# circuit_BLDCControl.net
KiCad netlist of a schematic drawn in Altium Designer
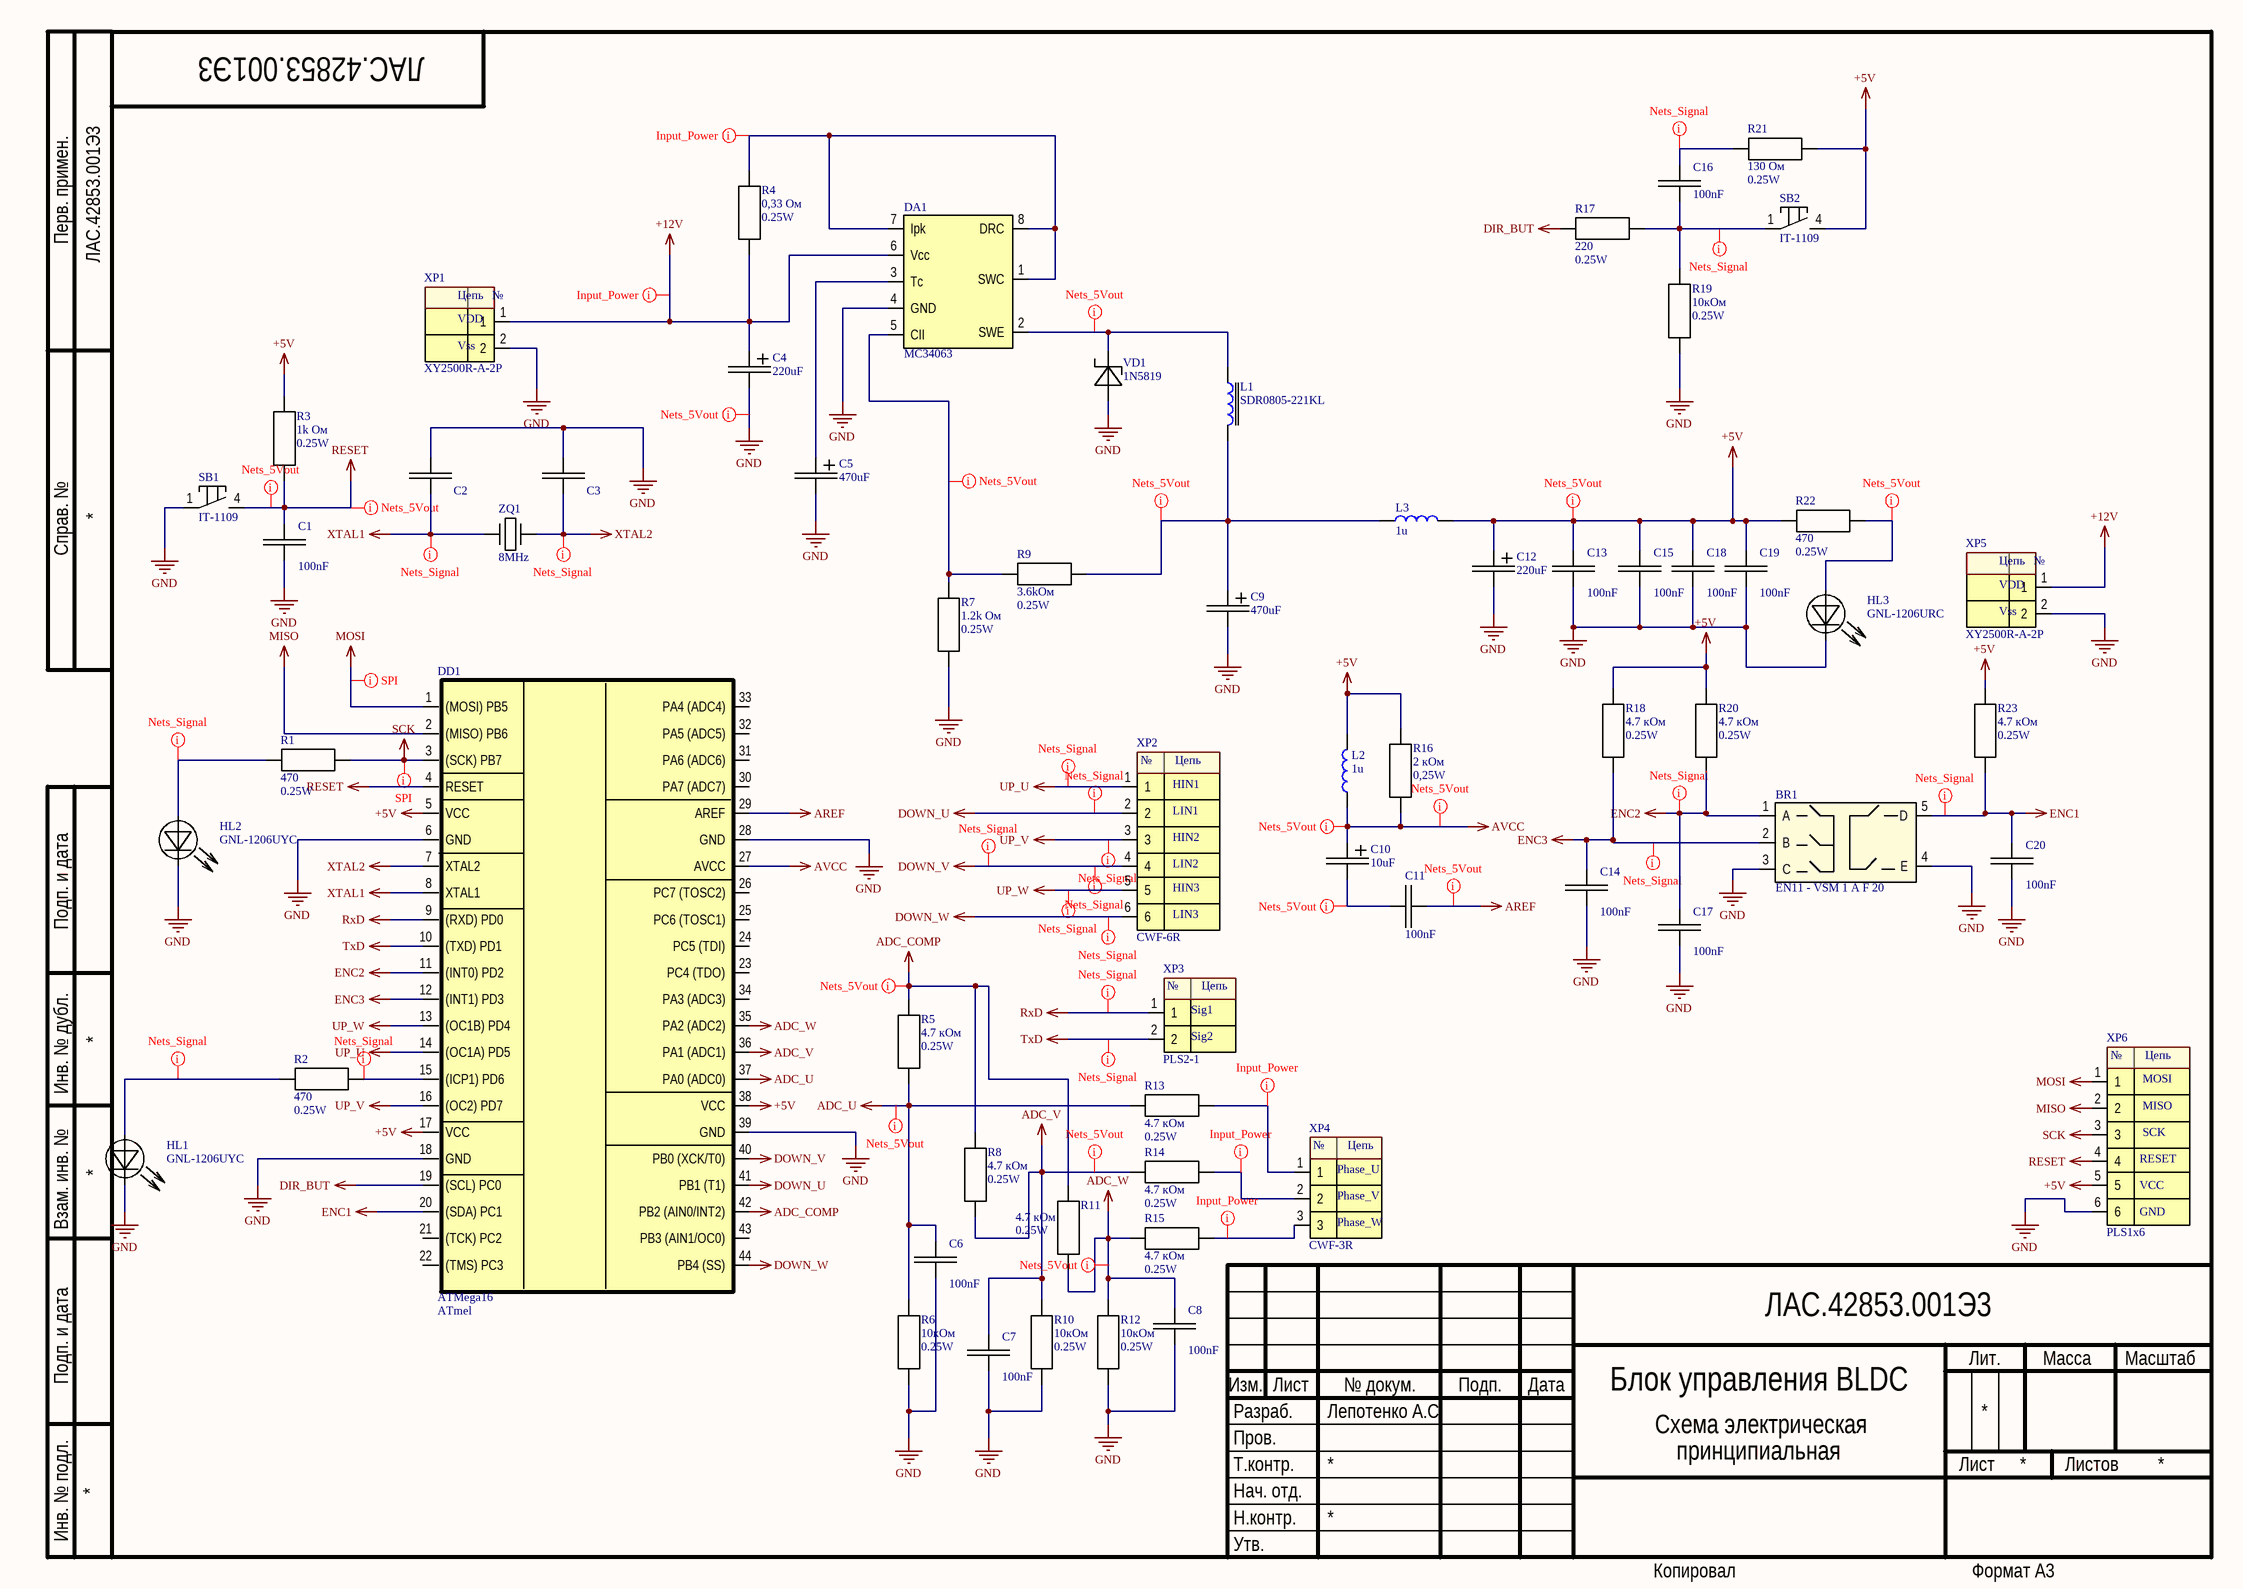
[diagram p0: circuit_BLDCControl.SchDoc]

(export (version "E")
  (design (tool "Eeschema 10.0.6"))
  (components
    (comp (ref "BR1")
      (value "EN11 - VSM 1 A F 20")
      (footprint "EN11-HSM")
      (fields (field (name "MANUFACTURER") "TTelectronics"))
      (libsource (lib "SchlibUGO") (part "Encoder"))
    )
    (comp (ref "C1")
      (value "100nF")
      (footprint "CAP1206")
      (fields
        (field (name "VOLTAGE") "50V")
        (field (name "PART NUMBER") "CL31B104KBCNNNC")
        (field (name "MANUFACTURER") "Samsung")
      )
      (libsource (lib "SchlibUGO") (part "Capasitor"))
    )
    (comp (ref "C2")
      (value "22pF")
      (footprint "CAP1206")
      (fields
        (field (name "VOLTAGE") "50V")
        (field (name "PART NUMBER") "NPO-50V")
        (field (name "MANUFACTURER") "Samsung")
      )
      (libsource (lib "SchlibUGO") (part "Capasitor"))
    )
    (comp (ref "C3")
      (value "22pF")
      (footprint "CAP1206")
      (fields
        (field (name "VOLTAGE") "50V")
        (field (name "PART NUMBER") "NPO-50V")
        (field (name "MANUFACTURER") "Samsung")
      )
      (libsource (lib "SchlibUGO") (part "Capasitor"))
    )
    (comp (ref "C4")
      (value "220uF")
      (footprint "CAPAE120103X105MTypeG")
      (fields
        (field (name "PART NUMBER") "220uF 35V 10x10")
        (field (name "MANUFACTURER") "Китай")
        (field (name "POWER") "10V")
      )
      (libsource (lib "SchlibUGO") (part "Capasitor Electrolit"))
    )
    (comp (ref "C5")
      (value "470uF")
      (footprint "CAPAE120103X105MTypeG")
      (fields
        (field (name "PART NUMBER") "B41121A3477M000")
        (field (name "MANUFACTURER") "EPCOS")
        (field (name "POWER") "25V")
      )
      (libsource (lib "SchlibUGO") (part "Capasitor Electrolit"))
    )
    (comp (ref "C6")
      (value "100nF")
      (footprint "CAP1206")
      (fields
        (field (name "VOLTAGE") "50V")
        (field (name "PART NUMBER") "CL31B104KBCNNNC")
        (field (name "MANUFACTURER") "Samsung")
      )
      (libsource (lib "SchlibUGO") (part "Capasitor"))
    )
    (comp (ref "C7")
      (value "100nF")
      (footprint "CAP1206")
      (fields
        (field (name "VOLTAGE") "50V")
        (field (name "PART NUMBER") "CL31B104KBCNNNC")
        (field (name "MANUFACTURER") "Samsung")
      )
      (libsource (lib "SchlibUGO") (part "Capasitor"))
    )
    (comp (ref "C8")
      (value "100nF")
      (footprint "CAP1206")
      (fields
        (field (name "VOLTAGE") "50V")
        (field (name "PART NUMBER") "CL31B104KBCNNNC")
        (field (name "MANUFACTURER") "Samsung")
      )
      (libsource (lib "SchlibUGO") (part "Capasitor"))
    )
    (comp (ref "C9")
      (value "470uF")
      (footprint "CAPAE120103X105MTypeG")
      (fields
        (field (name "PART NUMBER") "B41121A3477M000")
        (field (name "MANUFACTURER") "EPCOS")
        (field (name "POWER") "25V")
      )
      (libsource (lib "SchlibUGO") (part "Capasitor Electrolit"))
    )
    (comp (ref "C10")
      (value "10uF")
      (footprint "Type D")
      (fields
        (field (name "PART NUMBER") "D 10uF 25V 20")
        (field (name "MANUFACTURER") "Vishay")
        (field (name "POWER") "25V")
      )
      (libsource (lib "SchlibUGO") (part "Capasitor Electrolit"))
    )
    (comp (ref "C11")
      (value "100nF")
      (footprint "CAP1206")
      (fields
        (field (name "VOLTAGE") "50V")
        (field (name "PART NUMBER") "CL31B104KBCNNNC")
        (field (name "MANUFACTURER") "Samsung")
      )
      (libsource (lib "SchlibUGO") (part "Capasitor"))
    )
    (comp (ref "C12")
      (value "220uF")
      (footprint "CAPAE120103X105MTypeG")
      (fields
        (field (name "PART NUMBER") "220uF 35V 10x10")
        (field (name "MANUFACTURER") "Китай")
        (field (name "POWER") "10V")
      )
      (libsource (lib "SchlibUGO") (part "Capasitor Electrolit"))
    )
    (comp (ref "C13")
      (value "100nF")
      (footprint "CAP1206")
      (fields
        (field (name "VOLTAGE") "50V")
        (field (name "PART NUMBER") "CL31B104KBCNNNC")
        (field (name "MANUFACTURER") "Samsung")
      )
      (libsource (lib "SchlibUGO") (part "Capasitor"))
    )
    (comp (ref "C14")
      (value "100nF")
      (footprint "CAP1206")
      (fields
        (field (name "VOLTAGE") "50V")
        (field (name "PART NUMBER") "CL31B104KBCNNNC")
        (field (name "MANUFACTURER") "Samsung")
      )
      (libsource (lib "SchlibUGO") (part "Capasitor"))
    )
    (comp (ref "C15")
      (value "100nF")
      (footprint "CAP1206")
      (fields
        (field (name "VOLTAGE") "50V")
        (field (name "PART NUMBER") "CL31B104KBCNNNC")
        (field (name "MANUFACTURER") "Samsung")
      )
      (libsource (lib "SchlibUGO") (part "Capasitor"))
    )
    (comp (ref "C16")
      (value "100nF")
      (footprint "CAP1206")
      (fields
        (field (name "VOLTAGE") "50V")
        (field (name "PART NUMBER") "CL31B104KBCNNNC")
        (field (name "MANUFACTURER") "Samsung")
      )
      (libsource (lib "SchlibUGO") (part "Capasitor"))
    )
    (comp (ref "C17")
      (value "100nF")
      (footprint "CAP1206")
      (fields
        (field (name "VOLTAGE") "50V")
        (field (name "PART NUMBER") "CL31B104KBCNNNC")
        (field (name "MANUFACTURER") "Samsung")
      )
      (libsource (lib "SchlibUGO") (part "Capasitor"))
    )
    (comp (ref "C18")
      (value "100nF")
      (footprint "CAP1206")
      (fields
        (field (name "VOLTAGE") "50V")
        (field (name "PART NUMBER") "CL31B104KBCNNNC")
        (field (name "MANUFACTURER") "Samsung")
      )
      (libsource (lib "SchlibUGO") (part "Capasitor"))
    )
    (comp (ref "C19")
      (value "100nF")
      (footprint "CAP1206")
      (fields
        (field (name "VOLTAGE") "50V")
        (field (name "PART NUMBER") "CL31B104KBCNNNC")
        (field (name "MANUFACTURER") "Samsung")
      )
      (libsource (lib "SchlibUGO") (part "Capasitor"))
    )
    (comp (ref "C20")
      (value "100nF")
      (footprint "CAP1206")
      (fields
        (field (name "VOLTAGE") "50V")
        (field (name "PART NUMBER") "CL31B104KBCNNNC")
        (field (name "MANUFACTURER") "Samsung")
      )
      (libsource (lib "SchlibUGO") (part "Capasitor"))
    )
    (comp (ref "DA1")
      (value "MC34063")
      (footprint "SO-8")
      (fields (field (name "MANUFACTURER") "ON Semiconductor"))
      (libsource (lib "SchlibUGO") (part "MC34063"))
    )
    (comp (ref "DD1")
      (value "ATMega16")
      (footprint "TQFP80P1200X1200X120-44N")
      (fields (field (name "PART NUMBER") "ATMega16") (field (name "MANUFACTURER") "ATmel"))
      (libsource (lib "SchlibUGO") (part "ATMega 16"))
    )
    (comp (ref "HL1")
      (value "GNL-1206UYC")
      (footprint "LED1206")
      (fields (field (name "MANUFACTURER") "G-NOR"))
      (libsource (lib "SchlibUGO") (part "LED"))
    )
    (comp (ref "HL2")
      (value "GNL-1206UYC")
      (footprint "LED1206")
      (fields (field (name "MANUFACTURER") "G-NOR"))
      (libsource (lib "SchlibUGO") (part "LED"))
    )
    (comp (ref "HL3")
      (value "GNL-1206URC")
      (footprint "LED1206")
      (fields (field (name "MANUFACTURER") "G-NOR"))
      (libsource (lib "SchlibUGO") (part "LED"))
    )
    (comp (ref "L1")
      (value "SDR0805-221KL")
      (footprint "SDR0805")
      (fields (field (name "MANUFACTURER") "BOURNS"))
      (libsource (lib "SchlibUGO") (part "Induc_SD1105"))
    )
    (comp (ref "L2")
      (value "1u")
      (footprint "LQG15HN15NJ")
      (fields (field (name "PART NUMBER") "CM453232-1R0KL") (field (name "MANUFACTURER") "Bourns"))
      (libsource (lib "SchlibUGO") (part "Inductor"))
    )
    (comp (ref "L3")
      (value "1u")
      (footprint "LQG15HN15NJ")
      (fields (field (name "PART NUMBER") "CM453232-1R0KL") (field (name "MANUFACTURER") "Bourns"))
      (libsource (lib "SchlibUGO") (part "Inductor"))
    )
    (comp (ref "R1")
      (value "470")
      (footprint "1206")
      (fields
        (field (name "MANUFACTURER") "YAGEO")
        (field (name "PART NUMBER") "RC1206JR-07470RL")
        (field (name "POWER") "0.25W")
      )
      (libsource (lib "SchlibUGO") (part "Resistor"))
    )
    (comp (ref "R2")
      (value "470")
      (footprint "1206")
      (fields
        (field (name "MANUFACTURER") "YAGEO")
        (field (name "PART NUMBER") "RC1206JR-07470RL")
        (field (name "POWER") "0.25W")
      )
      (libsource (lib "SchlibUGO") (part "Resistor"))
    )
    (comp (ref "R3")
      (value "1k Ом")
      (footprint "1206")
      (fields
        (field (name "MANUFACTURER") "Royal Ohm")
        (field (name "PART NUMBER") "RC1206FR-071KL")
        (field (name "POWER") "0.25W")
      )
      (libsource (lib "SchlibUGO") (part "Resistor"))
    )
    (comp (ref "R4")
      (value "0,33 Ом")
      (footprint "1206")
      (fields
        (field (name "MANUFACTURER") "Royal Ohm")
        (field (name "PART NUMBER") "RC1206FR-12060R33")
        (field (name "POWER") "0.25W")
      )
      (libsource (lib "SchlibUGO") (part "Resistor"))
    )
    (comp (ref "R5")
      (value "4.7 кОм")
      (footprint "1206")
      (fields
        (field (name "MANUFACTURER") "YAGEO")
        (field (name "PART NUMBER") "RC1206JR-074K7L")
        (field (name "POWER") "0.25W")
      )
      (libsource (lib "SchlibUGO") (part "Resistor"))
    )
    (comp (ref "R6")
      (value "10кОм")
      (footprint "1206")
      (fields
        (field (name "MANUFACTURER") "YAGEO")
        (field (name "PART NUMBER") "RC1206JR-074K7L")
        (field (name "POWER") "0.25W")
      )
      (libsource (lib "SchlibUGO") (part "Resistor"))
    )
    (comp (ref "R7")
      (value "1.2k Ом")
      (footprint "1206")
      (fields
        (field (name "MANUFACTURER") "РФ")
        (field (name "PART NUMBER") "1206 1.2K")
        (field (name "POWER") "0.25W")
      )
      (libsource (lib "SchlibUGO") (part "Resistor"))
    )
    (comp (ref "R8")
      (value "4.7 кОм")
      (footprint "1206")
      (fields
        (field (name "MANUFACTURER") "YAGEO")
        (field (name "PART NUMBER") "RC1206JR-074K7L")
        (field (name "POWER") "0.25W")
      )
      (libsource (lib "SchlibUGO") (part "Resistor"))
    )
    (comp (ref "R9")
      (value "3.6kОм")
      (footprint "1206")
      (fields
        (field (name "MANUFACTURER") "РФ")
        (field (name "PART NUMBER") "1206 3.6K")
        (field (name "POWER") "0.25W")
      )
      (libsource (lib "SchlibUGO") (part "Resistor"))
    )
    (comp (ref "R10")
      (value "10кОм")
      (footprint "1206")
      (fields
        (field (name "MANUFACTURER") "YAGEO")
        (field (name "PART NUMBER") "RC1206JR-074K7L")
        (field (name "POWER") "0.25W")
      )
      (libsource (lib "SchlibUGO") (part "Resistor"))
    )
    (comp (ref "R11")
      (value "4.7 кОм")
      (footprint "1206")
      (fields
        (field (name "MANUFACTURER") "YAGEO")
        (field (name "PART NUMBER") "RC1206JR-074K7L")
        (field (name "POWER") "0.25W")
      )
      (libsource (lib "SchlibUGO") (part "Resistor"))
    )
    (comp (ref "R12")
      (value "10кОм")
      (footprint "1206")
      (fields
        (field (name "MANUFACTURER") "YAGEO")
        (field (name "PART NUMBER") "RC1206JR-074K7L")
        (field (name "POWER") "0.25W")
      )
      (libsource (lib "SchlibUGO") (part "Resistor"))
    )
    (comp (ref "R13")
      (value "4.7 кОм")
      (footprint "1206")
      (fields
        (field (name "MANUFACTURER") "YAGEO")
        (field (name "PART NUMBER") "RC1206JR-074K7L")
        (field (name "POWER") "0.25W")
      )
      (libsource (lib "SchlibUGO") (part "Resistor"))
    )
    (comp (ref "R14")
      (value "4.7 кОм")
      (footprint "1206")
      (fields
        (field (name "MANUFACTURER") "YAGEO")
        (field (name "PART NUMBER") "RC1206JR-074K7L")
        (field (name "POWER") "0.25W")
      )
      (libsource (lib "SchlibUGO") (part "Resistor"))
    )
    (comp (ref "R15")
      (value "4.7 кОм")
      (footprint "1206")
      (fields
        (field (name "MANUFACTURER") "YAGEO")
        (field (name "PART NUMBER") "RC1206JR-074K7L")
        (field (name "POWER") "0.25W")
      )
      (libsource (lib "SchlibUGO") (part "Resistor"))
    )
    (comp (ref "R16")
      (value "2 кОм")
      (footprint "1206")
      (fields
        (field (name "MANUFACTURER") "РФ")
        (field (name "PART NUMBER") "SMD 1206 2K")
        (field (name "POWER") "0,25W")
      )
      (libsource (lib "SchlibUGO") (part "Resistor"))
    )
    (comp (ref "R17")
      (value "220")
      (footprint "1206")
      (fields
        (field (name "MANUFACTURER") "Royal Ohm")
        (field (name "PART NUMBER") "HP06-220R5")
        (field (name "POWER") "0.25W")
      )
      (libsource (lib "SchlibUGO") (part "Resistor"))
    )
    (comp (ref "R18")
      (value "4.7 кОм")
      (footprint "1206")
      (fields
        (field (name "MANUFACTURER") "YAGEO")
        (field (name "PART NUMBER") "RC1206JR-074K7L")
        (field (name "POWER") "0.25W")
      )
      (libsource (lib "SchlibUGO") (part "Resistor"))
    )
    (comp (ref "R19")
      (value "10кОм")
      (footprint "1206")
      (fields
        (field (name "MANUFACTURER") "YAGEO")
        (field (name "PART NUMBER") "RC1206JR-0710KL")
        (field (name "POWER") "0.25W")
      )
      (libsource (lib "SchlibUGO") (part "Resistor"))
    )
    (comp (ref "R20")
      (value "4.7 кОм")
      (footprint "1206")
      (fields
        (field (name "MANUFACTURER") "YAGEO")
        (field (name "PART NUMBER") "RC1206JR-074K7L")
        (field (name "POWER") "0.25W")
      )
      (libsource (lib "SchlibUGO") (part "Resistor"))
    )
    (comp (ref "R21")
      (value "130 Ом")
      (footprint "1206")
      (fields
        (field (name "MANUFACTURER") "RF")
        (field (name "PART NUMBER") "130R")
        (field (name "POWER") "0.25W")
      )
      (libsource (lib "SchlibUGO") (part "Resistor"))
    )
    (comp (ref "R22")
      (value "470")
      (footprint "1206")
      (fields
        (field (name "MANUFACTURER") "YAGEO")
        (field (name "PART NUMBER") "RC1206JR-07470RL")
        (field (name "POWER") "0.25W")
      )
      (libsource (lib "SchlibUGO") (part "Resistor"))
    )
    (comp (ref "R23")
      (value "4.7 кОм")
      (footprint "1206")
      (fields
        (field (name "MANUFACTURER") "YAGEO")
        (field (name "PART NUMBER") "RC1206JR-074K7L")
        (field (name "POWER") "0.25W")
      )
      (libsource (lib "SchlibUGO") (part "Resistor"))
    )
    (comp (ref "SB1")
      (value "IT-1109")
      (footprint "KLS2")
      (fields (field (name "MANUFACTURER") "RUICHI"))
      (libsource (lib "SchlibUGO") (part "Button"))
    )
    (comp (ref "SB2")
      (value "IT-1109")
      (footprint "KLS2")
      (fields (field (name "MANUFACTURER") "RUICHI"))
      (libsource (lib "SchlibUGO") (part "Button"))
    )
    (comp (ref "VD1")
      (value "1N5819")
      (footprint "DO-41-V")
      (fields (field (name "MANUFACTURER") "GALAXY") (field (name "POWER") "1A"))
      (libsource (lib "Diode_Library") (part "1N5819"))
    )
    (comp (ref "XP1")
      (value "XY2500R-A-2P")
      (footprint "KLS2-EDR-500-2P")
      (fields (field (name "MANUFACTURER") "РБ"))
      (libsource (lib "SchlibUGO") (part "Connector_Power"))
    )
    (comp (ref "XP2")
      (value "CWF-6R")
      (footprint "CWF-6R")
      (fields (field (name "MANUFACTURER") "KLS"))
      (libsource (lib "SchlibUGO") (part "CWF-6R"))
    )
    (comp (ref "XP3")
      (value "PLS2-1")
      (footprint "PLS-2-1")
      (fields (field (name "MANUFACTURER") "KLS"))
      (libsource (lib "SchlibUGO") (part "PLS2-1"))
    )
    (comp (ref "XP4")
      (value "CWF-3R")
      (footprint "CWF-3R")
      (fields (field (name "MANUFACTURER") "KLS"))
      (libsource (lib "SchlibUGO") (part "CWF-3R"))
    )
    (comp (ref "XP5")
      (value "XY2500R-A-2P")
      (footprint "KLS2-EDR-500-2P")
      (fields (field (name "MANUFACTURER") "РБ"))
      (libsource (lib "SchlibUGO") (part "Connector_Power"))
    )
    (comp (ref "XP6")
      (value "PLS1x6")
      (footprint "PLS1x6")
      (fields (field (name "PART NUMBER") "KLS1x6") (field (name "MANUFACTURER") "KLS"))
      (libsource (lib "SchlibUGO") (part "PLS1x6"))
    )
    (comp (ref "ZQ1")
      (value "8MHz")
      (footprint "HC49-S")
      (fields (field (name "PART NUMBER") "HC49US-FF5F8.0000") (field (name "MANUFACTURER") "CHina"))
      (libsource (lib "SchlibUGO") (part "Rzanator"))
    )
  )
  (nets
    (net (code "1") (name "+5V") (class "Default")
      (node (ref "C12") (pin "1") (pinfunction "1_1") (pintype "passive"))
      (node (ref "C13") (pin "1") (pinfunction "1_1") (pintype "passive"))
      (node (ref "C15") (pin "1") (pinfunction "1_1") (pintype "passive"))
      (node (ref "C18") (pin "1") (pinfunction "1_1") (pintype "passive"))
      (node (ref "C19") (pin "1") (pinfunction "1_1") (pintype "passive"))
      (node (ref "DD1") (pin "17") (pinfunction "VCC_17") (pintype "passive"))
      (node (ref "DD1") (pin "38") (pinfunction "VCC_38") (pintype "passive"))
      (node (ref "DD1") (pin "5") (pinfunction "VCC_5") (pintype "passive"))
      (node (ref "L2") (pin "2") (pinfunction "2_2") (pintype "passive"))
      (node (ref "L3") (pin "2") (pinfunction "2_2") (pintype "passive"))
      (node (ref "R16") (pin "2") (pinfunction "2_2") (pintype "passive"))
      (node (ref "R18") (pin "2") (pinfunction "2_2") (pintype "passive"))
      (node (ref "R20") (pin "2") (pinfunction "2_2") (pintype "passive"))
      (node (ref "R21") (pin "2") (pinfunction "2_2") (pintype "passive"))
      (node (ref "R22") (pin "2") (pinfunction "2_2") (pintype "passive"))
      (node (ref "R23") (pin "2") (pinfunction "2_2") (pintype "passive"))
      (node (ref "R3") (pin "2") (pinfunction "2_2") (pintype "passive"))
      (node (ref "SB2") (pin "4") (pinfunction "4_4") (pintype "passive"))
      (node (ref "XP6") (pin "5") (pinfunction "5_5") (pintype "passive"))
    )
    (net (code "2") (name "+12V") (class "Default")
      (node (ref "C4") (pin "1") (pinfunction "1_1") (pintype "passive"))
      (node (ref "DA1") (pin "6") (pinfunction "Vcc_6") (pintype "passive"))
      (node (ref "R4") (pin "1") (pinfunction "1_1") (pintype "passive"))
      (node (ref "XP1") (pin "1") (pinfunction "1_1") (pintype "passive"))
      (node (ref "XP5") (pin "1") (pinfunction "1_1") (pintype "passive"))
    )
    (net (code "3") (name "ADC_COMP") (class "Default")
      (node (ref "DD1") (pin "42") (pinfunction "PB2_(AIN0/INT2)_42") (pintype "passive"))
      (node (ref "R11") (pin "1") (pinfunction "1_1") (pintype "passive"))
      (node (ref "R5") (pin "1") (pinfunction "1_1") (pintype "passive"))
      (node (ref "R8") (pin "1") (pinfunction "1_1") (pintype "passive"))
    )
    (net (code "4") (name "ADC_U") (class "Default")
      (node (ref "C6") (pin "1") (pinfunction "1_1") (pintype "passive"))
      (node (ref "DD1") (pin "37") (pinfunction "PA0_(ADC0)_37") (pintype "passive"))
      (node (ref "R13") (pin "2") (pinfunction "2_2") (pintype "passive"))
      (node (ref "R5") (pin "2") (pinfunction "2_2") (pintype "passive"))
      (node (ref "R6") (pin "1") (pinfunction "1_1") (pintype "passive"))
    )
    (net (code "5") (name "ADC_V") (class "Default")
      (node (ref "C7") (pin "1") (pinfunction "1_1") (pintype "passive"))
      (node (ref "DD1") (pin "36") (pinfunction "PA1_(ADC1)_36") (pintype "passive"))
      (node (ref "R10") (pin "1") (pinfunction "1_1") (pintype "passive"))
      (node (ref "R14") (pin "2") (pinfunction "2_2") (pintype "passive"))
      (node (ref "R8") (pin "2") (pinfunction "2_2") (pintype "passive"))
    )
    (net (code "6") (name "ADC_W") (class "Default")
      (node (ref "C8") (pin "1") (pinfunction "1_1") (pintype "passive"))
      (node (ref "DD1") (pin "35") (pinfunction "PA2_(ADC2)_35") (pintype "passive"))
      (node (ref "R11") (pin "2") (pinfunction "2_2") (pintype "passive"))
      (node (ref "R12") (pin "1") (pinfunction "1_1") (pintype "passive"))
      (node (ref "R15") (pin "2") (pinfunction "2_2") (pintype "passive"))
    )
    (net (code "7") (name "AREF") (class "Default")
      (node (ref "C11") (pin "2") (pinfunction "2_2") (pintype "passive"))
      (node (ref "DD1") (pin "29") (pinfunction "AREF_29") (pintype "passive"))
    )
    (net (code "8") (name "AVCC") (class "Default")
      (node (ref "C10") (pin "1") (pinfunction "1_1") (pintype "passive"))
      (node (ref "DD1") (pin "27") (pinfunction "AVCC_27") (pintype "passive"))
      (node (ref "L2") (pin "1") (pinfunction "1_1") (pintype "passive"))
      (node (ref "R16") (pin "1") (pinfunction "1_1") (pintype "passive"))
    )
    (net (code "9") (name "DIR_BUT") (class "Default")
      (node (ref "DD1") (pin "19") (pinfunction "(SCL)_PC0_19") (pintype "passive"))
      (node (ref "R17") (pin "1") (pinfunction "1_1") (pintype "passive"))
    )
    (net (code "10") (name "DOWN_U") (class "Default")
      (node (ref "DD1") (pin "41") (pinfunction "PB1_(T1)_41") (pintype "passive"))
      (node (ref "XP2") (pin "2") (pinfunction "2_2") (pintype "passive"))
    )
    (net (code "11") (name "DOWN_V") (class "Default")
      (node (ref "DD1") (pin "40") (pinfunction "PB0_(XCK/T0)_40") (pintype "passive"))
      (node (ref "XP2") (pin "4") (pinfunction "4_4") (pintype "passive"))
    )
    (net (code "12") (name "DOWN_W") (class "Default")
      (node (ref "DD1") (pin "44") (pinfunction "PB4_(SS)_44") (pintype "passive"))
      (node (ref "XP2") (pin "6") (pinfunction "6_6") (pintype "passive"))
    )
    (net (code "13") (name "ENC1") (class "Default")
      (node (ref "BR1") (pin "5") (pinfunction "D_5") (pintype "passive"))
      (node (ref "C20") (pin "1") (pinfunction "1_1") (pintype "passive"))
      (node (ref "DD1") (pin "20") (pinfunction "(SDA)_PC1_20") (pintype "passive"))
      (node (ref "R23") (pin "1") (pinfunction "1_1") (pintype "passive"))
    )
    (net (code "14") (name "ENC2") (class "Default")
      (node (ref "BR1") (pin "1") (pinfunction "A_1") (pintype "passive"))
      (node (ref "C17") (pin "1") (pinfunction "1_1") (pintype "passive"))
      (node (ref "DD1") (pin "11") (pinfunction "(INT0)_PD2_11") (pintype "passive"))
      (node (ref "R20") (pin "1") (pinfunction "1_1") (pintype "passive"))
    )
    (net (code "15") (name "ENC3") (class "Default")
      (node (ref "BR1") (pin "2") (pinfunction "B_2") (pintype "passive"))
      (node (ref "C14") (pin "1") (pinfunction "1_1") (pintype "passive"))
      (node (ref "DD1") (pin "12") (pinfunction "(INT1)_PD3_12") (pintype "passive"))
      (node (ref "R18") (pin "1") (pinfunction "1_1") (pintype "passive"))
    )
    (net (code "16") (name "GND") (class "Default")
      (node (ref "BR1") (pin "3") (pinfunction "C_3") (pintype "passive"))
      (node (ref "BR1") (pin "4") (pinfunction "E_4") (pintype "passive"))
      (node (ref "C1") (pin "2") (pinfunction "2_2") (pintype "passive"))
      (node (ref "C12") (pin "2") (pinfunction "2_2") (pintype "passive"))
      (node (ref "C13") (pin "2") (pinfunction "2_2") (pintype "passive"))
      (node (ref "C14") (pin "2") (pinfunction "2_2") (pintype "passive"))
      (node (ref "C15") (pin "2") (pinfunction "2_2") (pintype "passive"))
      (node (ref "C17") (pin "2") (pinfunction "2_2") (pintype "passive"))
      (node (ref "C18") (pin "2") (pinfunction "2_2") (pintype "passive"))
      (node (ref "C19") (pin "2") (pinfunction "2_2") (pintype "passive"))
      (node (ref "C2") (pin "1") (pinfunction "1_1") (pintype "passive"))
      (node (ref "C20") (pin "2") (pinfunction "2_2") (pintype "passive"))
      (node (ref "C3") (pin "1") (pinfunction "1_1") (pintype "passive"))
      (node (ref "C4") (pin "2") (pinfunction "2_2") (pintype "passive"))
      (node (ref "C5") (pin "2") (pinfunction "2_2") (pintype "passive"))
      (node (ref "C6") (pin "2") (pinfunction "2_2") (pintype "passive"))
      (node (ref "C7") (pin "2") (pinfunction "2_2") (pintype "passive"))
      (node (ref "C8") (pin "2") (pinfunction "2_2") (pintype "passive"))
      (node (ref "C9") (pin "2") (pinfunction "2_2") (pintype "passive"))
      (node (ref "DA1") (pin "4") (pinfunction "GND_4") (pintype "passive"))
      (node (ref "DD1") (pin "18") (pinfunction "GND_18") (pintype "passive"))
      (node (ref "DD1") (pin "28") (pinfunction "GND_28") (pintype "passive"))
      (node (ref "DD1") (pin "39") (pinfunction "GND_39") (pintype "passive"))
      (node (ref "DD1") (pin "6") (pinfunction "GND_6") (pintype "passive"))
      (node (ref "HL1") (pin "2") (pinfunction "2_2") (pintype "passive"))
      (node (ref "HL2") (pin "2") (pinfunction "2_2") (pintype "passive"))
      (node (ref "HL3") (pin "2") (pinfunction "2_2") (pintype "passive"))
      (node (ref "R10") (pin "2") (pinfunction "2_2") (pintype "passive"))
      (node (ref "R12") (pin "2") (pinfunction "2_2") (pintype "passive"))
      (node (ref "R19") (pin "1") (pinfunction "1_1") (pintype "passive"))
      (node (ref "R6") (pin "2") (pinfunction "2_2") (pintype "passive"))
      (node (ref "R7") (pin "1") (pinfunction "1_1") (pintype "passive"))
      (node (ref "SB1") (pin "1") (pinfunction "1_1") (pintype "passive"))
      (node (ref "VD1") (pin "1") (pinfunction "1_1") (pintype "passive"))
      (node (ref "XP1") (pin "2") (pinfunction "2_2") (pintype "passive"))
      (node (ref "XP5") (pin "2") (pinfunction "2_2") (pintype "passive"))
      (node (ref "XP6") (pin "6") (pinfunction "6_6") (pintype "passive"))
    )
    (net (code "17") (name "MISO") (class "Default")
      (node (ref "DD1") (pin "2") (pinfunction "(MISO)_PB6_2") (pintype "passive"))
      (node (ref "XP6") (pin "2") (pinfunction "2_2") (pintype "passive"))
    )
    (net (code "18") (name "MOSI") (class "Default")
      (node (ref "DD1") (pin "1") (pinfunction "(MOSI)_PB5_1") (pintype "passive"))
      (node (ref "XP6") (pin "1") (pinfunction "1_1") (pintype "passive"))
    )
    (net (code "19") (name "Net-(C9-Pad1)") (class "Default")
      (node (ref "C9") (pin "1") (pinfunction "1_1") (pintype "passive"))
      (node (ref "L1") (pin "2") (pinfunction "2_2") (pintype "passive"))
      (node (ref "L3") (pin "1") (pinfunction "1_1") (pintype "passive"))
      (node (ref "R9") (pin "2") (pinfunction "2_2") (pintype "passive"))
    )
    (net (code "20") (name "Net-(C10-Pad2)") (class "Default")
      (node (ref "C10") (pin "2") (pinfunction "2_2") (pintype "passive"))
      (node (ref "C11") (pin "1") (pinfunction "1_1") (pintype "passive"))
    )
    (net (code "21") (name "Net-(C16-Pad1)") (class "Default")
      (node (ref "C16") (pin "1") (pinfunction "1_1") (pintype "passive"))
      (node (ref "R21") (pin "1") (pinfunction "1_1") (pintype "passive"))
    )
    (net (code "22") (name "Net-(C16-Pad2)") (class "Default")
      (node (ref "C16") (pin "2") (pinfunction "2_2") (pintype "passive"))
      (node (ref "R17") (pin "2") (pinfunction "2_2") (pintype "passive"))
      (node (ref "R19") (pin "2") (pinfunction "2_2") (pintype "passive"))
      (node (ref "SB2") (pin "1") (pinfunction "1_1") (pintype "passive"))
    )
    (net (code "23") (name "Net-(DA1-CII)") (class "Default")
      (node (ref "DA1") (pin "5") (pinfunction "CII_5") (pintype "passive"))
      (node (ref "R7") (pin "2") (pinfunction "2_2") (pintype "passive"))
      (node (ref "R9") (pin "1") (pinfunction "1_1") (pintype "passive"))
    )
    (net (code "24") (name "Net-(DA1-DRC)") (class "Default")
      (node (ref "DA1") (pin "1") (pinfunction "SWC_1") (pintype "passive"))
      (node (ref "DA1") (pin "7") (pinfunction "Ipk_7") (pintype "passive"))
      (node (ref "DA1") (pin "8") (pinfunction "DRC_8") (pintype "passive"))
      (node (ref "R4") (pin "2") (pinfunction "2_2") (pintype "passive"))
    )
    (net (code "25") (name "Net-(DA1-SWE)") (class "Default")
      (node (ref "DA1") (pin "2") (pinfunction "SWE_2") (pintype "passive"))
      (node (ref "L1") (pin "1") (pinfunction "1_1") (pintype "passive"))
      (node (ref "VD1") (pin "2") (pinfunction "2_2") (pintype "passive"))
    )
    (net (code "26") (name "Net-(DA1-Tc)") (class "Default")
      (node (ref "C5") (pin "1") (pinfunction "1_1") (pintype "passive"))
      (node (ref "DA1") (pin "3") (pinfunction "Tc_3") (pintype "passive"))
    )
    (net (code "27") (name "Net-(DD1-(ICP1)_PD6)") (class "Default")
      (node (ref "DD1") (pin "15") (pinfunction "(ICP1)_PD6_15") (pintype "passive"))
      (node (ref "R2") (pin "1") (pinfunction "1_1") (pintype "passive"))
    )
    (net (code "28") (name "Net-(HL1-Pad1)") (class "Default")
      (node (ref "HL1") (pin "1") (pinfunction "1_1") (pintype "passive"))
      (node (ref "R2") (pin "2") (pinfunction "2_2") (pintype "passive"))
    )
    (net (code "29") (name "Net-(HL2-Pad1)") (class "Default")
      (node (ref "HL2") (pin "1") (pinfunction "1_1") (pintype "passive"))
      (node (ref "R1") (pin "2") (pinfunction "2_2") (pintype "passive"))
    )
    (net (code "30") (name "Net-(HL3-Pad1)") (class "Default")
      (node (ref "HL3") (pin "1") (pinfunction "1_1") (pintype "passive"))
      (node (ref "R22") (pin "1") (pinfunction "1_1") (pintype "passive"))
    )
    (net (code "31") (name "Net-(R13-Pad1)") (class "Default")
      (node (ref "R13") (pin "1") (pinfunction "1_1") (pintype "passive"))
      (node (ref "XP4") (pin "1") (pinfunction "1_1") (pintype "passive"))
    )
    (net (code "32") (name "Net-(R14-Pad1)") (class "Default")
      (node (ref "R14") (pin "1") (pinfunction "1_1") (pintype "passive"))
      (node (ref "XP4") (pin "2") (pinfunction "2_2") (pintype "passive"))
    )
    (net (code "33") (name "Net-(R15-Pad1)") (class "Default")
      (node (ref "R15") (pin "1") (pinfunction "1_1") (pintype "passive"))
      (node (ref "XP4") (pin "3") (pinfunction "3_3") (pintype "passive"))
    )
    (net (code "34") (name "RESET") (class "Default")
      (node (ref "C1") (pin "1") (pinfunction "1_1") (pintype "passive"))
      (node (ref "DD1") (pin "4") (pinfunction "RESET_4") (pintype "passive"))
      (node (ref "R3") (pin "1") (pinfunction "1_1") (pintype "passive"))
      (node (ref "SB1") (pin "4") (pinfunction "4_4") (pintype "passive"))
      (node (ref "XP6") (pin "4") (pinfunction "4_4") (pintype "passive"))
    )
    (net (code "35") (name "RxD") (class "Default")
      (node (ref "DD1") (pin "9") (pinfunction "(RXD)_PD0_9") (pintype "passive"))
      (node (ref "XP3") (pin "1") (pinfunction "1_1") (pintype "passive"))
    )
    (net (code "36") (name "SCK") (class "Default")
      (node (ref "DD1") (pin "3") (pinfunction "(SCK)_PB7_3") (pintype "passive"))
      (node (ref "R1") (pin "1") (pinfunction "1_1") (pintype "passive"))
      (node (ref "XP6") (pin "3") (pinfunction "3_3") (pintype "passive"))
    )
    (net (code "37") (name "TxD") (class "Default")
      (node (ref "DD1") (pin "10") (pinfunction "(TXD)_PD1_10") (pintype "passive"))
      (node (ref "XP3") (pin "2") (pinfunction "2_2") (pintype "passive"))
    )
    (net (code "38") (name "UP_U") (class "Default")
      (node (ref "DD1") (pin "14") (pinfunction "(OC1A)_PD5_14") (pintype "passive"))
      (node (ref "XP2") (pin "1") (pinfunction "1_1") (pintype "passive"))
    )
    (net (code "39") (name "UP_V") (class "Default")
      (node (ref "DD1") (pin "16") (pinfunction "(OC2)_PD7_16") (pintype "passive"))
      (node (ref "XP2") (pin "3") (pinfunction "3_3") (pintype "passive"))
    )
    (net (code "40") (name "UP_W") (class "Default")
      (node (ref "DD1") (pin "13") (pinfunction "(OC1B)_PD4_13") (pintype "passive"))
      (node (ref "XP2") (pin "5") (pinfunction "5_5") (pintype "passive"))
    )
    (net (code "41") (name "XTAL1") (class "Default")
      (node (ref "C2") (pin "2") (pinfunction "2_2") (pintype "passive"))
      (node (ref "DD1") (pin "8") (pinfunction "XTAL1_8") (pintype "passive"))
      (node (ref "ZQ1") (pin "1") (pinfunction "1_1") (pintype "passive"))
    )
    (net (code "42") (name "XTAL2") (class "Default")
      (node (ref "C3") (pin "2") (pinfunction "2_2") (pintype "passive"))
      (node (ref "DD1") (pin "7") (pinfunction "XTAL2_7") (pintype "passive"))
      (node (ref "ZQ1") (pin "3") (pinfunction "2_3") (pintype "passive"))
    )
    (net (code "43") (name "unconnected-(DD1-(TCK)_PC2-Pad21)") (class "Default")
      (node (ref "DD1") (pin "21") (pinfunction "(TCK)_PC2_21") (pintype "passive"))
    )
    (net (code "44") (name "unconnected-(DD1-(TMS)_PC3-Pad22)") (class "Default")
      (node (ref "DD1") (pin "22") (pinfunction "(TMS)_PC3_22") (pintype "passive"))
    )
    (net (code "45") (name "unconnected-(DD1-PA3_(ADC3)-Pad34)") (class "Default")
      (node (ref "DD1") (pin "34") (pinfunction "PA3_(ADC3)_34") (pintype "passive"))
    )
    (net (code "46") (name "unconnected-(DD1-PA4_(ADC4)-Pad33)") (class "Default")
      (node (ref "DD1") (pin "33") (pinfunction "PA4_(ADC4)_33") (pintype "passive"))
    )
    (net (code "47") (name "unconnected-(DD1-PA5_(ADC5)-Pad32)") (class "Default")
      (node (ref "DD1") (pin "32") (pinfunction "PA5_(ADC5)_32") (pintype "passive"))
    )
    (net (code "48") (name "unconnected-(DD1-PA6_(ADC6)-Pad31)") (class "Default")
      (node (ref "DD1") (pin "31") (pinfunction "PA6_(ADC6)_31") (pintype "passive"))
    )
    (net (code "49") (name "unconnected-(DD1-PA7_(ADC7)-Pad30)") (class "Default")
      (node (ref "DD1") (pin "30") (pinfunction "PA7_(ADC7)_30") (pintype "passive"))
    )
    (net (code "50") (name "unconnected-(DD1-PB3_(AIN1{slash}OC0)-Pad43)") (class "Default")
      (node (ref "DD1") (pin "43") (pinfunction "PB3_(AIN1/OC0)_43") (pintype "passive"))
    )
    (net (code "51") (name "unconnected-(DD1-PC4_(TDO)-Pad23)") (class "Default")
      (node (ref "DD1") (pin "23") (pinfunction "PC4_(TDO)_23") (pintype "passive"))
    )
    (net (code "52") (name "unconnected-(DD1-PC5_(TDI)-Pad24)") (class "Default")
      (node (ref "DD1") (pin "24") (pinfunction "PC5_(TDI)_24") (pintype "passive"))
    )
    (net (code "53") (name "unconnected-(DD1-PC6_(TOSC1)-Pad25)") (class "Default")
      (node (ref "DD1") (pin "25") (pinfunction "PC6_(TOSC1)_25") (pintype "passive"))
    )
    (net (code "54") (name "unconnected-(DD1-PC7_(TOSC2)-Pad26)") (class "Default")
      (node (ref "DD1") (pin "26") (pinfunction "PC7_(TOSC2)_26") (pintype "passive"))
    )
  )
)
